# Sheet1.net
KiCad netlist of a schematic drawn in Altium Designer
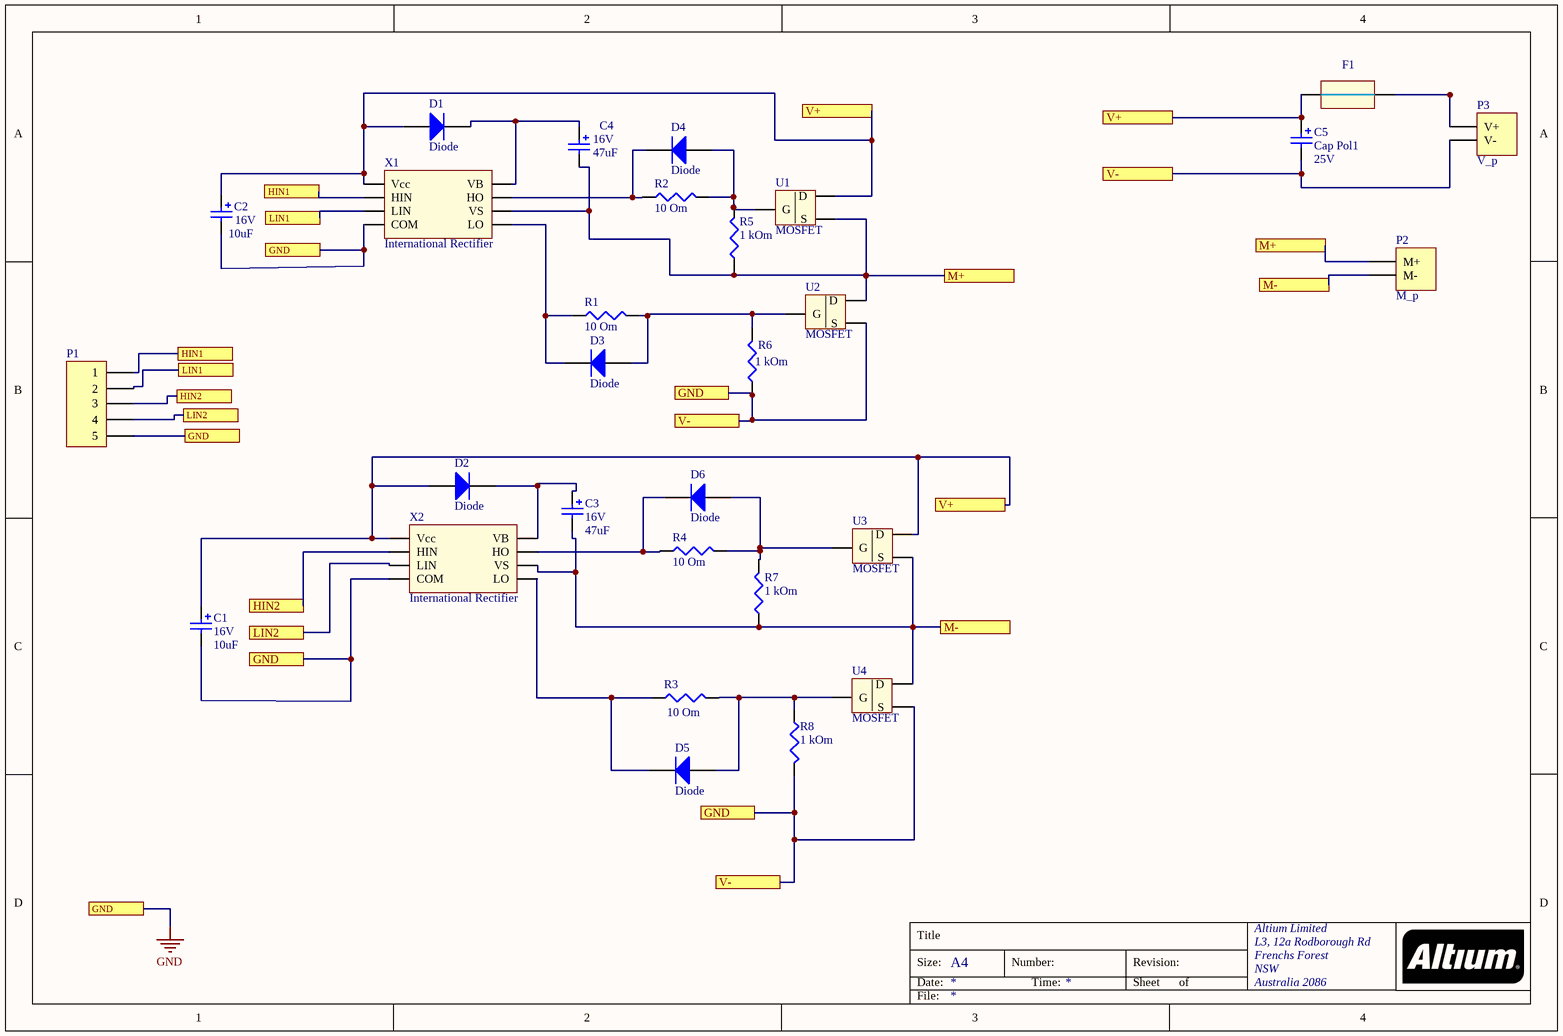
[diagram p0: Sheet1.SchDoc]

(export (version "E")
  (design (tool "Eeschema 10.0.6"))
  (components
    (comp (ref "C1")
      (value "16V")
      (footprint "smd cap 10")
      (description "Polarized Capacitor (Radial)")
      (fields (field (name "ALTIUM_VALUE") "10uF") (field (name "PUBLISHER") "Altium Limited"))
      (libsource (lib "Schlib1") (part "Cap smd_10"))
    )
    (comp (ref "C2")
      (value "16V")
      (footprint "smd cap 10")
      (description "Polarized Capacitor (Radial)")
      (fields (field (name "ALTIUM_VALUE") "10uF") (field (name "PUBLISHER") "Altium Limited"))
      (libsource (lib "Schlib1") (part "Cap smd_10"))
    )
    (comp (ref "C3")
      (value "16V")
      (footprint "smd cap 47")
      (description "Polarized Capacitor (Radial)")
      (fields (field (name "ALTIUM_VALUE") "47uF") (field (name "PUBLISHER") "Altium Limited"))
      (libsource (lib "Schlib1") (part "Cap smd_47"))
    )
    (comp (ref "C4")
      (value "16V")
      (footprint "smd cap 47")
      (description "Polarized Capacitor (Radial)")
      (fields (field (name "ALTIUM_VALUE") "47uF") (field (name "PUBLISHER") "Altium Limited"))
      (libsource (lib "Schlib1") (part "Cap smd_47"))
    )
    (comp (ref "C5")
      (value "Cap Pol1")
      (footprint "Cap El")
      (description "Polarized Capacitor (Radial)")
      (fields (field (name "ALTIUM_VALUE") "25V") (field (name "PUBLISHER") "Altium Limited"))
      (libsource (lib "Schlib1") (part "Cap smd"))
    )
    (comp (ref "D1")
      (value "Diode")
      (footprint "SOD123")
      (description "Default Diode")
      (fields (field (name "PUBLISHER") "Altium Limited"))
      (libsource (lib "Schlib1") (part "Diode"))
    )
    (comp (ref "D2")
      (value "Diode")
      (footprint "SOD123")
      (description "Default Diode")
      (fields (field (name "PUBLISHER") "Altium Limited"))
      (libsource (lib "Schlib1") (part "Diode"))
    )
    (comp (ref "D3")
      (value "Diode")
      (footprint "SOD123")
      (description "Default Diode")
      (fields (field (name "PUBLISHER") "Altium Limited"))
      (libsource (lib "Schlib1") (part "Diode"))
    )
    (comp (ref "D4")
      (value "Diode")
      (footprint "SOD123")
      (description "Default Diode")
      (fields (field (name "PUBLISHER") "Altium Limited"))
      (libsource (lib "Schlib1") (part "Diode"))
    )
    (comp (ref "D5")
      (value "Diode")
      (footprint "SOD123")
      (description "Default Diode")
      (fields (field (name "PUBLISHER") "Altium Limited"))
      (libsource (lib "Schlib1") (part "Diode"))
    )
    (comp (ref "D6")
      (value "Diode")
      (footprint "SOD123")
      (description "Default Diode")
      (fields (field (name "PUBLISHER") "Altium Limited"))
      (libsource (lib "Schlib1") (part "Diode"))
    )
    (comp (ref "F1") (value "Fuse") (footprint "FH-101") (libsource (lib "Schlib1") (part "FH-101")))
    (comp (ref "P1")
      (value "jst5")
      (footprint "JST5")
      (description "Header, 5-Pin")
      (fields (field (name "PUBLISHER") "Altium Limited"))
      (libsource (lib "Schlib1") (part "jst5"))
    )
    (comp (ref "P2") (value "M_p") (footprint "M_pin") (libsource (lib "Schlib1") (part "M_p")))
    (comp (ref "P3") (value "V_p") (footprint "V_pin") (libsource (lib "Schlib1") (part "V_p")))
    (comp (ref "R1")
      (value "10 Om")
      (footprint "14-1210")
      (description "Resistor")
      (fields (field (name "PUBLISHER") "Altium Limited"))
      (libsource (lib "Schlib1") (part "Res3"))
    )
    (comp (ref "R2")
      (value "10 Om")
      (footprint "14-1210")
      (description "Resistor")
      (fields (field (name "PUBLISHER") "Altium Limited"))
      (libsource (lib "Schlib1") (part "Res3"))
    )
    (comp (ref "R3")
      (value "10 Om")
      (footprint "14-1210")
      (description "Resistor")
      (fields (field (name "Comment") "Res3") (field (name "PUBLISHER") "Altium Limited"))
      (libsource (lib "Schlib1") (part "Res3"))
    )
    (comp (ref "R4")
      (value "10 Om")
      (footprint "14-1210")
      (description "Resistor")
      (fields (field (name "PUBLISHER") "Altium Limited"))
      (libsource (lib "Schlib1") (part "Res3"))
    )
    (comp (ref "R5")
      (value "1 kOm")
      (footprint "14-1210")
      (description "Resistor")
      (fields (field (name "PUBLISHER") "Altium Limited"))
      (libsource (lib "Schlib1") (part "Res3"))
    )
    (comp (ref "R6")
      (value "1 kOm")
      (footprint "14-1210")
      (description "Resistor")
      (fields (field (name "Comment") "Res3") (field (name "PUBLISHER") "Altium Limited"))
      (libsource (lib "Schlib1") (part "Res3"))
    )
    (comp (ref "R7")
      (value "1 kOm")
      (footprint "14-1210")
      (description "Resistor")
      (fields (field (name "PUBLISHER") "Altium Limited"))
      (libsource (lib "Schlib1") (part "Res3"))
    )
    (comp (ref "R8")
      (value "1 kOm")
      (footprint "14-1210")
      (description "Resistor")
      (fields (field (name "PUBLISHER") "Altium Limited"))
      (libsource (lib "Schlib1") (part "Res3"))
    )
    (comp (ref "U1")
      (value "MOSFET")
      (footprint "SMD220_10CTQ150")
      (libsource (lib "Schlib1") (part "IRFZ14PBF"))
    )
    (comp (ref "U2")
      (value "MOSFET")
      (footprint "SMD220_10CTQ150")
      (libsource (lib "Schlib1") (part "IRFZ14PBF"))
    )
    (comp (ref "U3")
      (value "MOSFET")
      (footprint "SMD220_10CTQ150")
      (libsource (lib "Schlib1") (part "IRFZ14PBF"))
    )
    (comp (ref "U4")
      (value "MOSFET")
      (footprint "SMD220_10CTQ150")
      (libsource (lib "Schlib1") (part "IRFZ14PBF"))
    )
    (comp (ref "X1")
      (value "International Rectifier")
      (footprint "SOIC8")
      (libsource (lib "Schlib1") (part "IR2101SPBF"))
    )
    (comp (ref "X2")
      (value "International Rectifier")
      (footprint "SOIC8")
      (libsource (lib "Schlib1") (part "IR2101SPBF"))
    )
  )
  (nets
    (net (code "1") (name "/HIN1") (class "Default")
      (node (ref "P1") (pin "1") (pinfunction "1_1") (pintype "passive"))
      (node (ref "X1") (pin "2") (pinfunction "HIN_2") (pintype "passive"))
    )
    (net (code "2") (name "/HIN2") (class "Default")
      (node (ref "P1") (pin "3") (pinfunction "3_3") (pintype "passive"))
      (node (ref "X2") (pin "2") (pinfunction "HIN_2") (pintype "passive"))
    )
    (net (code "3") (name "/LIN1") (class "Default")
      (node (ref "P1") (pin "2") (pinfunction "2_2") (pintype "passive"))
      (node (ref "X1") (pin "3") (pinfunction "LIN_3") (pintype "passive"))
    )
    (net (code "4") (name "/LIN2") (class "Default")
      (node (ref "P1") (pin "4") (pinfunction "4_4") (pintype "passive"))
      (node (ref "X2") (pin "3") (pinfunction "LIN_3") (pintype "passive"))
    )
    (net (code "5") (name "/M+") (class "Default")
      (node (ref "C4") (pin "2") (pinfunction "2_2") (pintype "passive"))
      (node (ref "P2") (pin "1") (pinfunction "M+_1") (pintype "passive"))
      (node (ref "R5") (pin "1") (pinfunction "1_1") (pintype "passive"))
      (node (ref "U1") (pin "3") (pinfunction "S_3") (pintype "passive"))
      (node (ref "U2") (pin "2") (pinfunction "D_2") (pintype "passive"))
      (node (ref "X1") (pin "6") (pinfunction "VS_6") (pintype "passive"))
    )
    (net (code "6") (name "/M-") (class "Default")
      (node (ref "C3") (pin "2") (pinfunction "2_2") (pintype "passive"))
      (node (ref "P2") (pin "2") (pinfunction "M-_2") (pintype "passive"))
      (node (ref "R7") (pin "1") (pinfunction "1_1") (pintype "passive"))
      (node (ref "U3") (pin "3") (pinfunction "S_3") (pintype "passive"))
      (node (ref "U4") (pin "2") (pinfunction "D_2") (pintype "passive"))
      (node (ref "X2") (pin "6") (pinfunction "VS_6") (pintype "passive"))
    )
    (net (code "7") (name "/V+") (class "Default")
      (node (ref "C1") (pin "1") (pinfunction "1_1") (pintype "passive"))
      (node (ref "C2") (pin "1") (pinfunction "1_1") (pintype "passive"))
      (node (ref "C5") (pin "1") (pinfunction "1_1") (pintype "passive"))
      (node (ref "D1") (pin "1") (pinfunction "A_1") (pintype "passive"))
      (node (ref "D2") (pin "1") (pinfunction "A_1") (pintype "passive"))
      (node (ref "F1") (pin "1") (pinfunction "1_1") (pintype "passive"))
      (node (ref "U1") (pin "2") (pinfunction "D_2") (pintype "passive"))
      (node (ref "U3") (pin "2") (pinfunction "D_2") (pintype "passive"))
      (node (ref "X1") (pin "1") (pinfunction "Vcc_1") (pintype "passive"))
      (node (ref "X2") (pin "1") (pinfunction "Vcc_1") (pintype "passive"))
    )
    (net (code "8") (name "GND") (class "Default")
      (node (ref "C1") (pin "2") (pinfunction "2_2") (pintype "passive"))
      (node (ref "C2") (pin "2") (pinfunction "2_2") (pintype "passive"))
      (node (ref "C5") (pin "2") (pinfunction "2_2") (pintype "passive"))
      (node (ref "P1") (pin "5") (pinfunction "5_5") (pintype "passive"))
      (node (ref "P3") (pin "2") (pinfunction "V-_2") (pintype "passive"))
      (node (ref "R6") (pin "1") (pinfunction "1_1") (pintype "passive"))
      (node (ref "R8") (pin "2") (pinfunction "2_2") (pintype "passive"))
      (node (ref "U2") (pin "3") (pinfunction "S_3") (pintype "passive"))
      (node (ref "U4") (pin "3") (pinfunction "S_3") (pintype "passive"))
      (node (ref "X1") (pin "4") (pinfunction "COM_4") (pintype "passive"))
      (node (ref "X2") (pin "4") (pinfunction "COM_4") (pintype "passive"))
    )
    (net (code "9") (name "Net-(D1-K)") (class "Default")
      (node (ref "C4") (pin "1") (pinfunction "1_1") (pintype "passive"))
      (node (ref "D1") (pin "2") (pinfunction "K_2") (pintype "passive"))
      (node (ref "X1") (pin "8") (pinfunction "VB_8") (pintype "passive"))
    )
    (net (code "10") (name "Net-(D2-K)") (class "Default")
      (node (ref "C3") (pin "1") (pinfunction "1_1") (pintype "passive"))
      (node (ref "D2") (pin "2") (pinfunction "K_2") (pintype "passive"))
      (node (ref "X2") (pin "8") (pinfunction "VB_8") (pintype "passive"))
    )
    (net (code "11") (name "Net-(D3-A)") (class "Default")
      (node (ref "D3") (pin "1") (pinfunction "A_1") (pintype "passive"))
      (node (ref "R1") (pin "2") (pinfunction "2_2") (pintype "passive"))
      (node (ref "R6") (pin "2") (pinfunction "2_2") (pintype "passive"))
      (node (ref "U2") (pin "1") (pinfunction "G_1") (pintype "passive"))
    )
    (net (code "12") (name "Net-(D3-K)") (class "Default")
      (node (ref "D3") (pin "2") (pinfunction "K_2") (pintype "passive"))
      (node (ref "R1") (pin "1") (pinfunction "1_1") (pintype "passive"))
      (node (ref "X1") (pin "5") (pinfunction "LO_5") (pintype "passive"))
    )
    (net (code "13") (name "Net-(D4-A)") (class "Default")
      (node (ref "D4") (pin "1") (pinfunction "A_1") (pintype "passive"))
      (node (ref "R2") (pin "2") (pinfunction "2_2") (pintype "passive"))
      (node (ref "R5") (pin "2") (pinfunction "2_2") (pintype "passive"))
      (node (ref "U1") (pin "1") (pinfunction "G_1") (pintype "passive"))
    )
    (net (code "14") (name "Net-(D4-K)") (class "Default")
      (node (ref "D4") (pin "2") (pinfunction "K_2") (pintype "passive"))
      (node (ref "R2") (pin "1") (pinfunction "1_1") (pintype "passive"))
      (node (ref "X1") (pin "7") (pinfunction "HO_7") (pintype "passive"))
    )
    (net (code "15") (name "Net-(D5-A)") (class "Default")
      (node (ref "D5") (pin "1") (pinfunction "A_1") (pintype "passive"))
      (node (ref "R3") (pin "2") (pinfunction "2_2") (pintype "passive"))
      (node (ref "R8") (pin "1") (pinfunction "1_1") (pintype "passive"))
      (node (ref "U4") (pin "1") (pinfunction "G_1") (pintype "passive"))
    )
    (net (code "16") (name "Net-(D5-K)") (class "Default")
      (node (ref "D5") (pin "2") (pinfunction "K_2") (pintype "passive"))
      (node (ref "R3") (pin "1") (pinfunction "1_1") (pintype "passive"))
      (node (ref "X2") (pin "5") (pinfunction "LO_5") (pintype "passive"))
    )
    (net (code "17") (name "Net-(D6-A)") (class "Default")
      (node (ref "D6") (pin "1") (pinfunction "A_1") (pintype "passive"))
      (node (ref "R4") (pin "2") (pinfunction "2_2") (pintype "passive"))
      (node (ref "R7") (pin "2") (pinfunction "2_2") (pintype "passive"))
      (node (ref "U3") (pin "1") (pinfunction "G_1") (pintype "passive"))
    )
    (net (code "18") (name "Net-(D6-K)") (class "Default")
      (node (ref "D6") (pin "2") (pinfunction "K_2") (pintype "passive"))
      (node (ref "R4") (pin "1") (pinfunction "1_1") (pintype "passive"))
      (node (ref "X2") (pin "7") (pinfunction "HO_7") (pintype "passive"))
    )
    (net (code "19") (name "Net-(P3-V+)") (class "Default")
      (node (ref "F1") (pin "2") (pinfunction "2_2") (pintype "passive"))
      (node (ref "P3") (pin "1") (pinfunction "V+_1") (pintype "passive"))
    )
  )
)
